# SCH_nfc-card-viswathiha_2024-10-10.net
KiCad netlist of a schematic drawn in EasyEDA
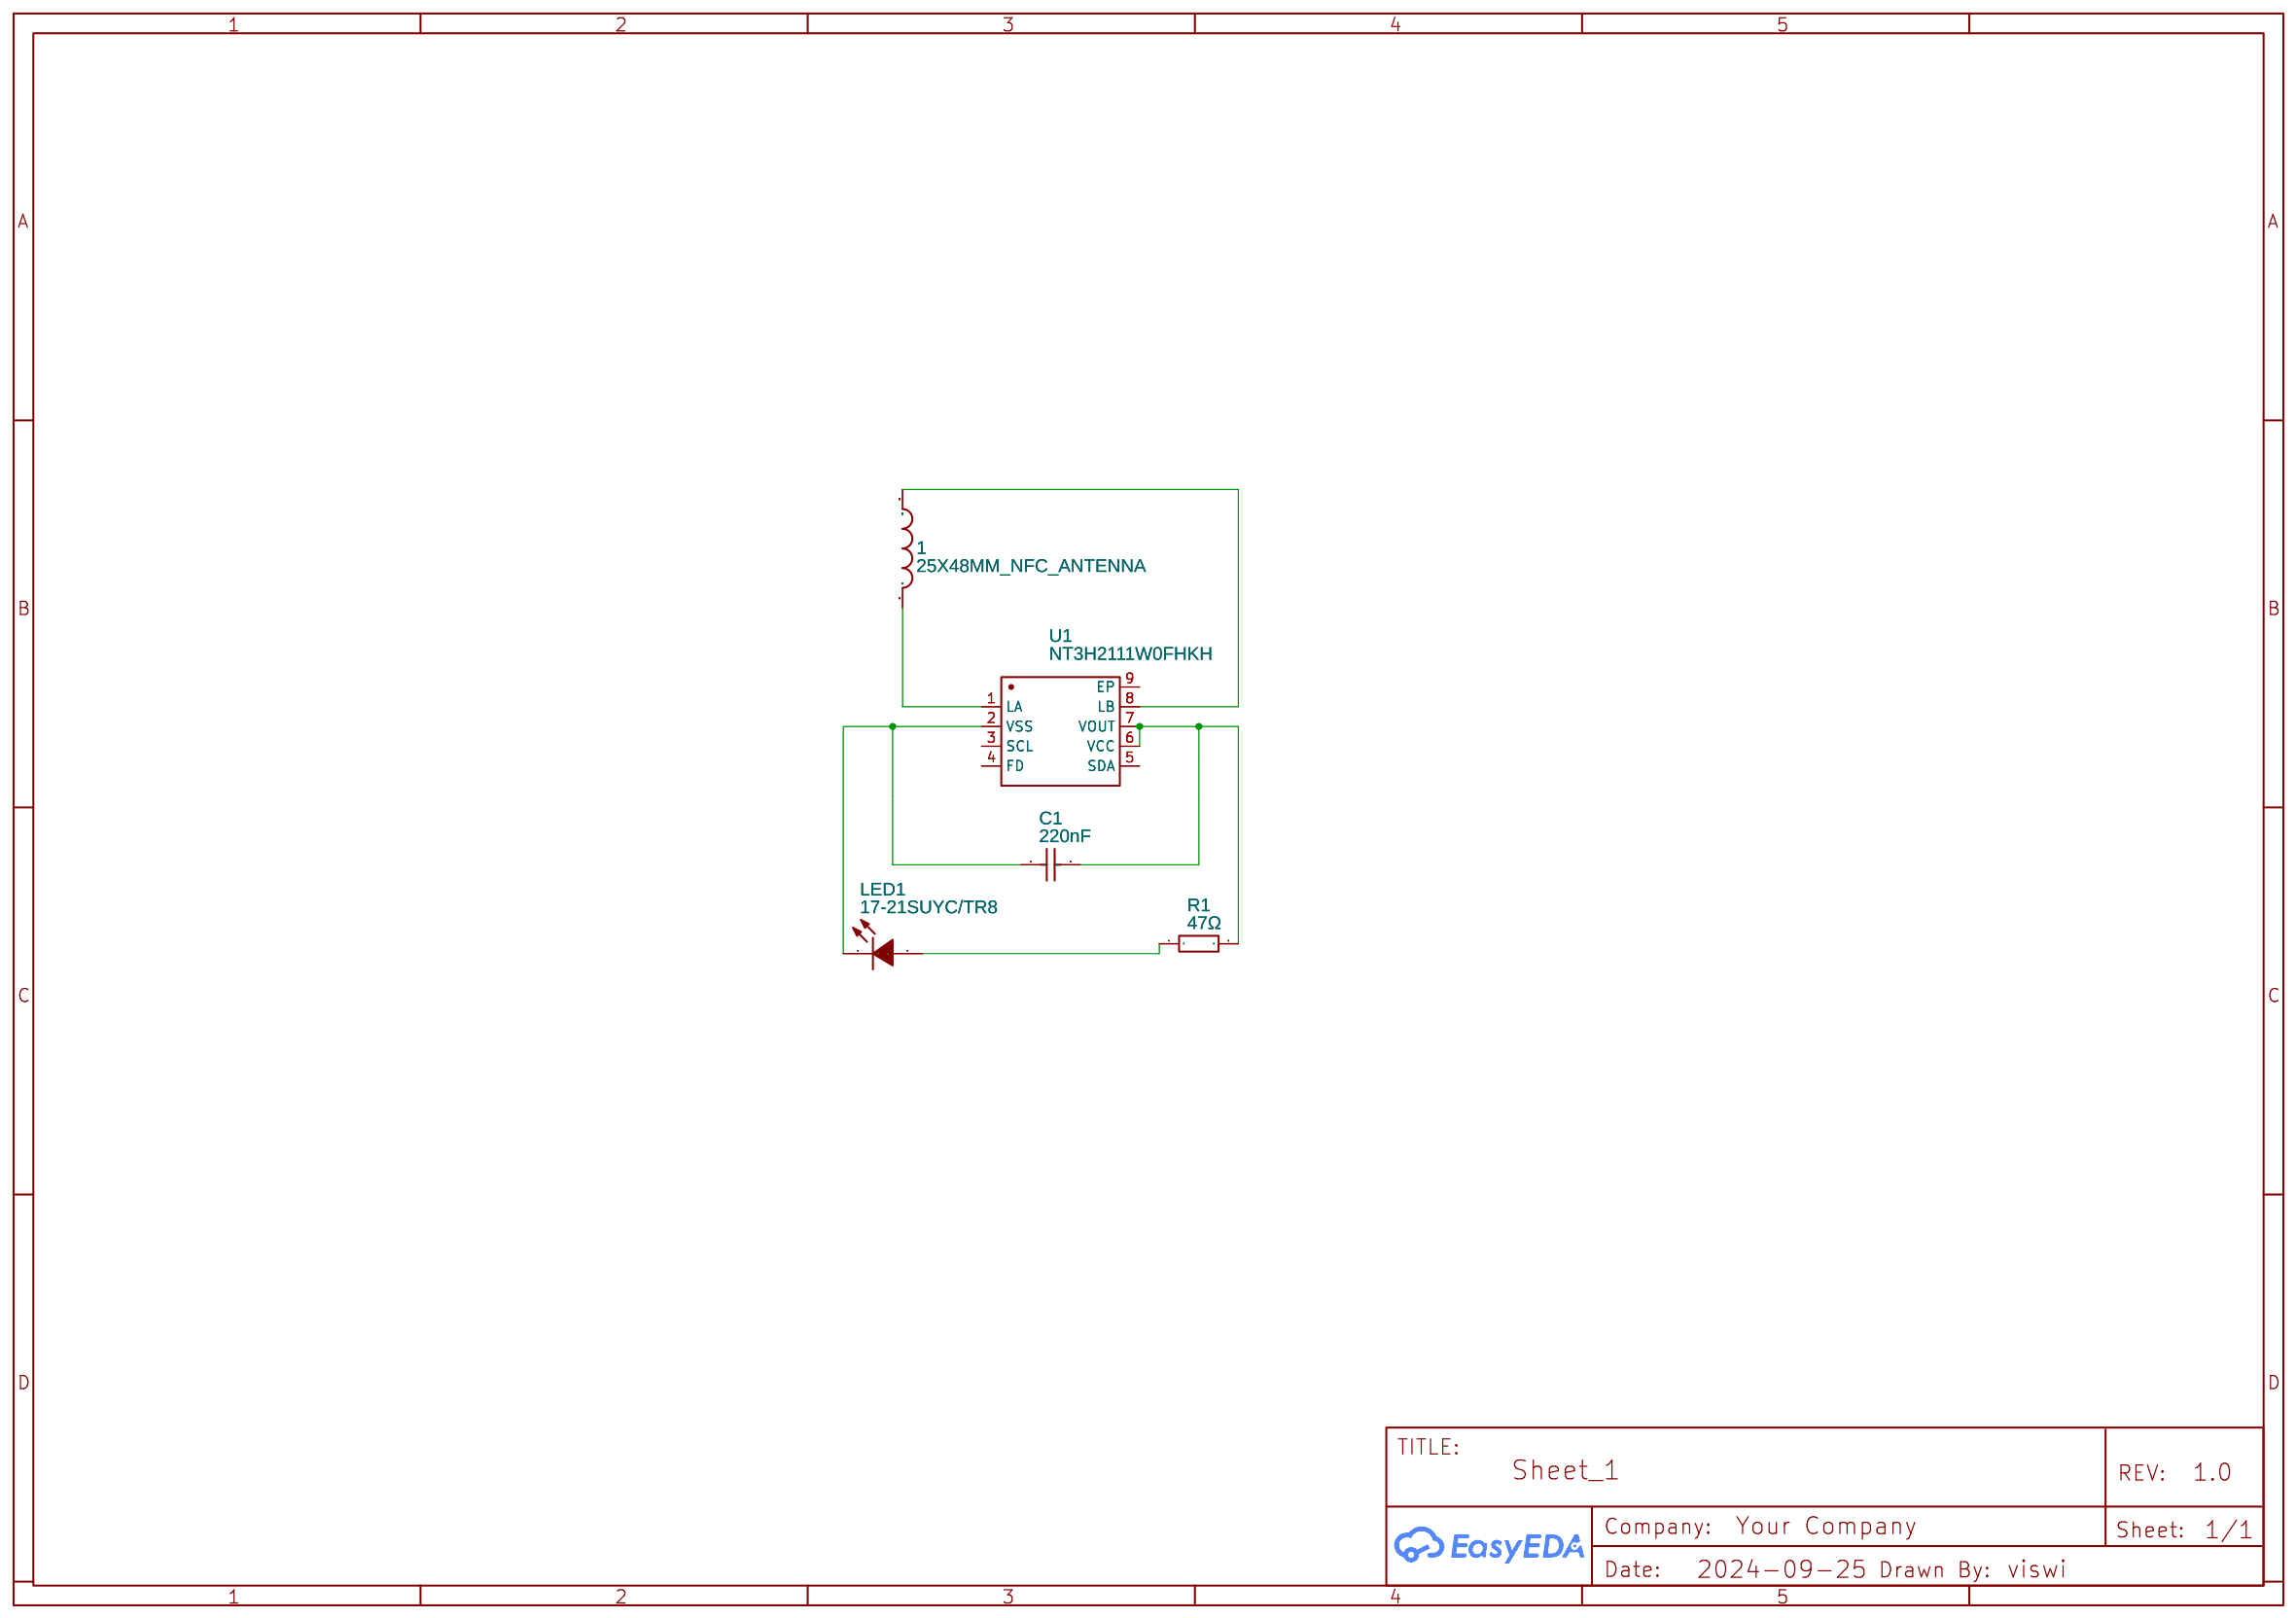
[diagram p0: schematic sheet]

(export (version "E")
  (design (tool "Eeschema 10.0.6"))
  (components
    (comp (ref "1") (value "25X48MM_NFC_ANTENNA") (libsource (lib "") (part "25X48MM_NFC_ANTENNA")))
    (comp (ref "C1")
      (value "220nF")
      (fields
        (field (name "Manufacturer Part") "CL10B224KA8NNNC")
        (field (name "Manufacturer") "SAMSUNG(三星)")
      )
      (libsource (lib "") (part "CL10B224KA8NNNC"))
    )
    (comp (ref "LED1")
      (value "17-21SUYC/TR8")
      (fields (field (name "Manufacturer Part") "KT-0805黄灯") (field (name "Manufacturer") "KENTO"))
      (libsource (lib "") (part "17-21SUYC/TR8"))
    )
    (comp (ref "R1")
      (value "47Ω")
      (fields
        (field (name "Manufacturer Part") "0603WAF470JT5E")
        (field (name "Manufacturer") "UNI-ROYAL(厚声)")
      )
      (libsource (lib "") (part "0603WAF470JT5E"))
    )
    (comp (ref "U1")
      (value "NT3H2111W0FHKH")
      (fields (field (name "Manufacturer") "NXP(恩智浦)"))
      (libsource (lib "") (part "NT3H2111W0FHKH"))
    )
  )
  (nets
    (net (code "1") (name "Net-(LED1-+)") (class "Default")
      (node (ref "LED1") (pin "1") (pinfunction "+_1") (pintype "unspecified"))
      (node (ref "R1") (pin "1") (pinfunction "1_1") (pintype "input"))
    )
    (net (code "2") (name "Net-(LED1--)") (class "Default")
      (node (ref "C1") (pin "1") (pinfunction "1_1") (pintype "input"))
      (node (ref "LED1") (pin "2") (pinfunction "-_2") (pintype "unspecified"))
      (node (ref "U1") (pin "2") (pinfunction "VSS_2") (pintype "unspecified"))
    )
    (net (code "3") (name "Net-(U1-LA)") (class "Default")
      (node (ref "1") (pin "P$2") (pinfunction "P$2_P$2") (pintype "bidirectional"))
      (node (ref "U1") (pin "1") (pinfunction "LA_1") (pintype "unspecified"))
    )
    (net (code "4") (name "Net-(U1-LB)") (class "Default")
      (node (ref "1") (pin "P$1") (pinfunction "P$1_P$1") (pintype "bidirectional"))
      (node (ref "U1") (pin "8") (pinfunction "LB_8") (pintype "unspecified"))
    )
    (net (code "5") (name "Net-(U1-VCC)") (class "Default")
      (node (ref "C1") (pin "2") (pinfunction "2_2") (pintype "input"))
      (node (ref "R1") (pin "2") (pinfunction "2_2") (pintype "input"))
      (node (ref "U1") (pin "6") (pinfunction "VCC_6") (pintype "unspecified"))
      (node (ref "U1") (pin "7") (pinfunction "VOUT_7") (pintype "unspecified"))
    )
    (net (code "6") (name "unconnected-(U1-EP-Pad9)") (class "Default")
      (node (ref "U1") (pin "9") (pinfunction "EP_9") (pintype "unspecified"))
    )
    (net (code "7") (name "unconnected-(U1-FD-Pad4)") (class "Default")
      (node (ref "U1") (pin "4") (pinfunction "FD_4") (pintype "unspecified"))
    )
    (net (code "8") (name "unconnected-(U1-SCL-Pad3)") (class "Default")
      (node (ref "U1") (pin "3") (pinfunction "SCL_3") (pintype "unspecified"))
    )
    (net (code "9") (name "unconnected-(U1-SDA-Pad5)") (class "Default")
      (node (ref "U1") (pin "5") (pinfunction "SDA_5") (pintype "unspecified"))
    )
  )
)
